# IR_Light_Controller.net
KiCad netlist of a schematic drawn in EAGLE
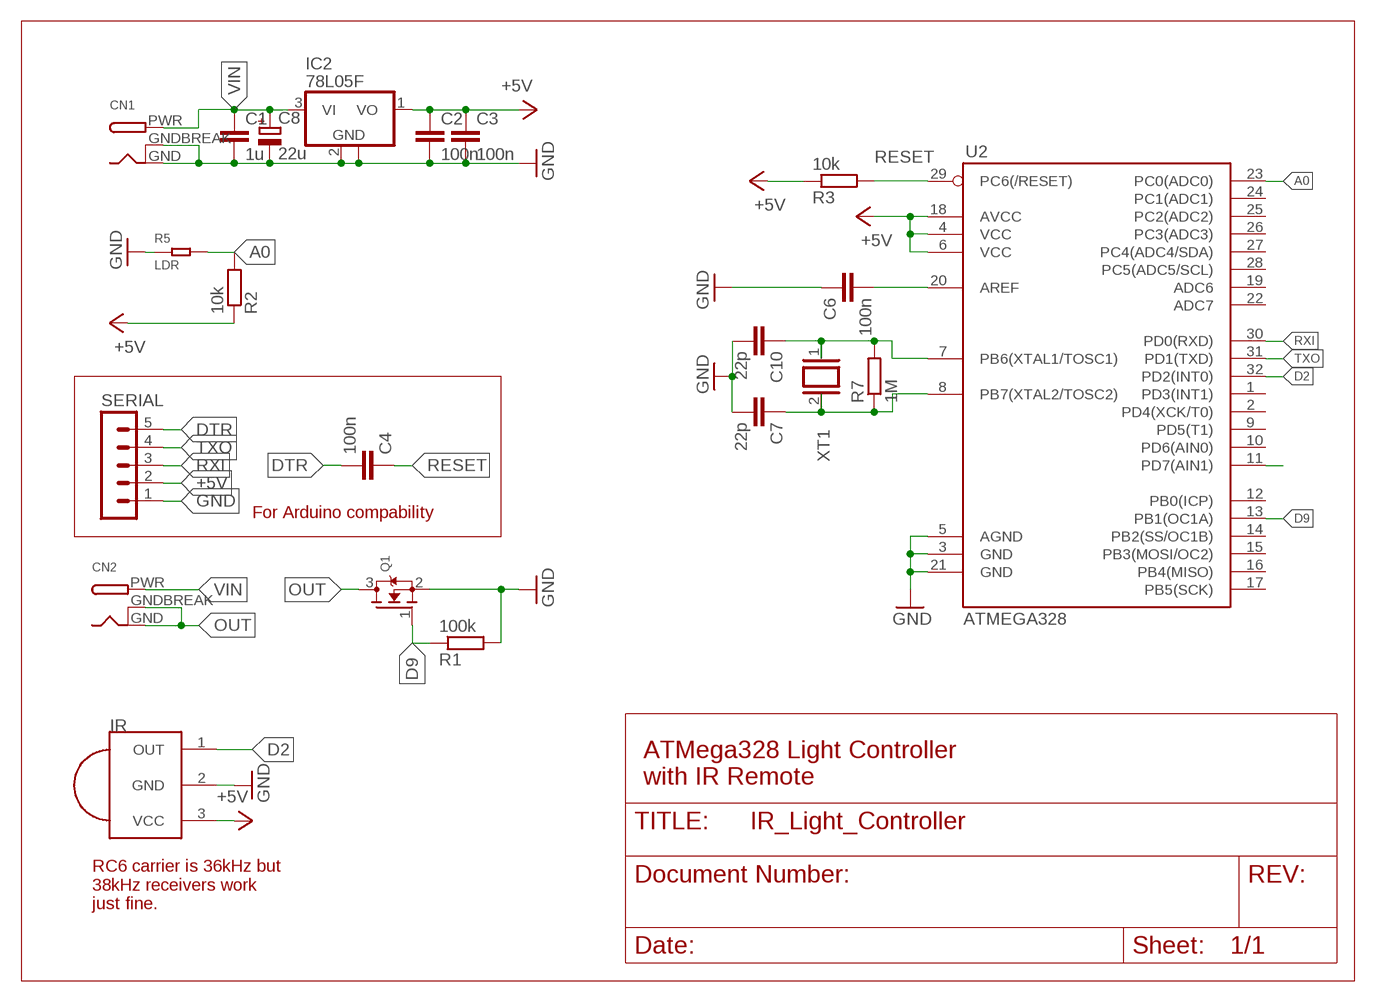
[diagram p0: schematic, sheet 1]

(export (version "E")
  (design (tool "Eeschema 10.0.6"))
  (components
    (comp (ref "C1")
      (value "1u")
      (footprint "eagle-import:C0805")
      (libsource (lib "eagle-import") (part "C-EUC0805"))
    )
    (comp (ref "C2")
      (value "100n")
      (footprint "eagle-import:C0805")
      (libsource (lib "eagle-import") (part "C-EUC0805"))
    )
    (comp (ref "C3")
      (value "100n")
      (footprint "eagle-import:C0805")
      (libsource (lib "eagle-import") (part "C-EUC0805"))
    )
    (comp (ref "C4")
      (value "100n")
      (footprint "eagle-import:C0805K")
      (libsource (lib "eagle-import") (part "C-EUC0805K"))
    )
    (comp (ref "C6")
      (value "100n")
      (footprint "eagle-import:C0805K")
      (libsource (lib "eagle-import") (part "C-EUC0805K"))
    )
    (comp (ref "C7")
      (value "22p")
      (footprint "eagle-import:C0805K")
      (libsource (lib "eagle-import") (part "C-EUC0805K"))
    )
    (comp (ref "C8")
      (value "22u")
      (footprint "eagle-import:E2-4")
      (libsource (lib "eagle-import") (part "CPOL-EUE2-4"))
    )
    (comp (ref "C10")
      (value "22p")
      (footprint "eagle-import:C0805K")
      (libsource (lib "eagle-import") (part "C-EUC0805K"))
    )
    (comp (ref "CN1")
      (value "DCBARRELPTH")
      (footprint "eagle-import:DCJACK_2MM_PTH")
      (libsource (lib "eagle-import") (part "DCBARRELPTH"))
    )
    (comp (ref "CN2")
      (value "DCBARRELPTH")
      (footprint "eagle-import:DCJACK_2MM_PTH")
      (libsource (lib "eagle-import") (part "DCBARRELPTH"))
    )
    (comp (ref "IC2")
      (value "78L05F")
      (footprint "eagle-import:SOT89")
      (libsource (lib "eagle-import") (part "78LF05"))
    )
    (comp (ref "IR")
      (value "PNA460XM")
      (footprint "eagle-import:PNA460XM")
      (libsource (lib "eagle-import") (part "PNA460XM"))
    )
    (comp (ref "Q1")
      (value "MOSFET-NWAVE")
      (footprint "eagle-import:SOT23-W")
      (libsource (lib "eagle-import") (part "MOSFET-NWAVE"))
    )
    (comp (ref "R1")
      (value "100k")
      (footprint "eagle-import:M0805")
      (libsource (lib "eagle-import") (part "R-EU_M0805"))
    )
    (comp (ref "R2")
      (value "10k")
      (footprint "eagle-import:M0805")
      (libsource (lib "eagle-import") (part "R-EU_M0805"))
    )
    (comp (ref "R3")
      (value "10k")
      (footprint "eagle-import:M0805")
      (libsource (lib "eagle-import") (part "R-EU_M0805"))
    )
    (comp (ref "R5")
      (value "LDR")
      (footprint "eagle-import:PR-2.8-4.2X4.9MM")
      (fields (field (name "MPN") "LDR-VT90N2"))
      (libsource (lib "eagle-import") (part "DIP-RES-LDR(2P-D2.3X3.7MM)"))
    )
    (comp (ref "R7")
      (value "1M")
      (footprint "eagle-import:M0805")
      (libsource (lib "eagle-import") (part "R-EU_M0805"))
    )
    (comp (ref "SERIAL")
      (value "MA05-1")
      (footprint "eagle-import:MA05-1")
      (libsource (lib "eagle-import") (part "MA05-1"))
    )
    (comp (ref "U2")
      (value "ATMEGA328")
      (footprint "eagle-import:TQFP32-08")
      (libsource (lib "eagle-import") (part "ATMEGA168"))
    )
    (comp (ref "XT1")
      (value "XTAL/S")
      (footprint "eagle-import:QS")
      (libsource (lib "eagle-import") (part "XTAL/S"))
    )
  )
  (nets
    (net (code "1") (name "+5V") (class "Default")
      (node (ref "C2") (pin "1") (pinfunction "1_1") (pintype "passive"))
      (node (ref "C3") (pin "1") (pinfunction "1_1") (pintype "passive"))
      (node (ref "IC2") (pin "1") (pinfunction "VO_1") (pintype "passive"))
      (node (ref "IR") (pin "3") (pinfunction "VCC_3") (pintype "power_in"))
      (node (ref "R2") (pin "1") (pinfunction "1_1") (pintype "passive"))
      (node (ref "R3") (pin "1") (pinfunction "1_1") (pintype "passive"))
      (node (ref "SERIAL") (pin "2") (pinfunction "2_2") (pintype "passive"))
      (node (ref "U2") (pin "18") (pinfunction "AVCC_18") (pintype "bidirectional"))
      (node (ref "U2") (pin "4") (pinfunction "VCC_4") (pintype "bidirectional"))
      (node (ref "U2") (pin "6") (pinfunction "VCC_6") (pintype "bidirectional"))
    )
    (net (code "2") (name "A0") (class "Default")
      (node (ref "R2") (pin "2") (pinfunction "2_2") (pintype "passive"))
      (node (ref "R5") (pin "2") (pinfunction "2_2") (pintype "passive"))
      (node (ref "U2") (pin "23") (pinfunction "PC0(ADC0)_23") (pintype "bidirectional"))
    )
    (net (code "3") (name "D2") (class "Default")
      (node (ref "IR") (pin "1") (pinfunction "OUT_1") (pintype "output"))
      (node (ref "U2") (pin "32") (pinfunction "PD2(INT0)_32") (pintype "bidirectional"))
    )
    (net (code "4") (name "D9") (class "Default")
      (node (ref "Q1") (pin "1") (pinfunction "G_1") (pintype "bidirectional"))
      (node (ref "R1") (pin "1") (pinfunction "1_1") (pintype "passive"))
      (node (ref "U2") (pin "13") (pinfunction "PB1(OC1A)_13") (pintype "bidirectional"))
    )
    (net (code "5") (name "DTR") (class "Default")
      (node (ref "C4") (pin "2") (pinfunction "2_2") (pintype "passive"))
      (node (ref "SERIAL") (pin "5") (pinfunction "5_5") (pintype "passive"))
    )
    (net (code "6") (name "GND") (class "Default")
      (node (ref "C1") (pin "2") (pinfunction "2_2") (pintype "passive"))
      (node (ref "C10") (pin "2") (pinfunction "2_2") (pintype "passive"))
      (node (ref "C2") (pin "2") (pinfunction "2_2") (pintype "passive"))
      (node (ref "C3") (pin "2") (pinfunction "2_2") (pintype "passive"))
      (node (ref "C6") (pin "1") (pinfunction "1_1") (pintype "passive"))
      (node (ref "C7") (pin "2") (pinfunction "2_2") (pintype "passive"))
      (node (ref "C8") (pin "-") (pinfunction "-_-") (pintype "passive"))
      (node (ref "CN1") (pin "GND") (pinfunction "GND_GND") (pintype "power_in"))
      (node (ref "CN1") (pin "GNDBREAK") (pinfunction "GNDBREAK_GNDBREAK") (pintype "power_in"))
      (node (ref "IC2") (pin "2") (pinfunction "GND_2") (pintype "passive"))
      (node (ref "IC2") (pin "2@1") (pinfunction "GND_2@1") (pintype "passive"))
      (node (ref "IR") (pin "2") (pinfunction "GND_2") (pintype "power_in"))
      (node (ref "Q1") (pin "2") (pinfunction "S_2") (pintype "bidirectional"))
      (node (ref "R1") (pin "2") (pinfunction "2_2") (pintype "passive"))
      (node (ref "R5") (pin "1") (pinfunction "1_1") (pintype "passive"))
      (node (ref "SERIAL") (pin "1") (pinfunction "1_1") (pintype "passive"))
      (node (ref "U2") (pin "21") (pinfunction "GND_21") (pintype "bidirectional"))
      (node (ref "U2") (pin "3") (pinfunction "GND_3") (pintype "bidirectional"))
      (node (ref "U2") (pin "5") (pinfunction "AGND_5") (pintype "bidirectional"))
    )
    (net (code "7") (name "Net-(U2-AREF)") (class "Default")
      (node (ref "C6") (pin "2") (pinfunction "2_2") (pintype "passive"))
      (node (ref "U2") (pin "20") (pinfunction "AREF_20") (pintype "bidirectional"))
    )
    (net (code "8") (name "Net-(U2-PB6(XTAL1{slash}TOSC1))") (class "Default")
      (node (ref "C10") (pin "1") (pinfunction "1_1") (pintype "passive"))
      (node (ref "R7") (pin "2") (pinfunction "2_2") (pintype "passive"))
      (node (ref "U2") (pin "7") (pinfunction "PB6(XTAL1/TOSC1)_7") (pintype "bidirectional"))
      (node (ref "XT1") (pin "1") (pinfunction "1_1") (pintype "passive"))
    )
    (net (code "9") (name "Net-(U2-PB7(XTAL2{slash}TOSC2))") (class "Default")
      (node (ref "C7") (pin "1") (pinfunction "1_1") (pintype "passive"))
      (node (ref "R7") (pin "1") (pinfunction "1_1") (pintype "passive"))
      (node (ref "U2") (pin "8") (pinfunction "PB7(XTAL2/TOSC2)_8") (pintype "bidirectional"))
      (node (ref "XT1") (pin "2") (pinfunction "2_2") (pintype "passive"))
    )
    (net (code "10") (name "OUT") (class "Default")
      (node (ref "CN2") (pin "GND") (pinfunction "GND_GND") (pintype "power_in"))
      (node (ref "CN2") (pin "GNDBREAK") (pinfunction "GNDBREAK_GNDBREAK") (pintype "power_in"))
      (node (ref "Q1") (pin "3") (pinfunction "D_3") (pintype "bidirectional"))
    )
    (net (code "11") (name "RESET") (class "Default")
      (node (ref "C4") (pin "1") (pinfunction "1_1") (pintype "passive"))
      (node (ref "R3") (pin "2") (pinfunction "2_2") (pintype "passive"))
      (node (ref "U2") (pin "29") (pinfunction "PC6(/RESET)_29") (pintype "bidirectional"))
    )
    (net (code "12") (name "RXI") (class "Default")
      (node (ref "SERIAL") (pin "3") (pinfunction "3_3") (pintype "passive"))
      (node (ref "U2") (pin "30") (pinfunction "PD0(RXD)_30") (pintype "bidirectional"))
    )
    (net (code "13") (name "TXO") (class "Default")
      (node (ref "SERIAL") (pin "4") (pinfunction "4_4") (pintype "passive"))
      (node (ref "U2") (pin "31") (pinfunction "PD1(TXD)_31") (pintype "bidirectional"))
    )
    (net (code "14") (name "VIN") (class "Default")
      (node (ref "C1") (pin "1") (pinfunction "1_1") (pintype "passive"))
      (node (ref "C8") (pin "+") (pinfunction "+_+") (pintype "passive"))
      (node (ref "CN1") (pin "PWR") (pinfunction "PWR_PWR") (pintype "power_in"))
      (node (ref "CN2") (pin "PWR") (pinfunction "PWR_PWR") (pintype "power_in"))
      (node (ref "IC2") (pin "3") (pinfunction "VI_3") (pintype "input"))
    )
    (net (code "15") (name "unconnected-(U2-ADC6-Pad19)") (class "Default")
      (node (ref "U2") (pin "19") (pinfunction "ADC6_19") (pintype "bidirectional"))
    )
    (net (code "16") (name "unconnected-(U2-ADC7-Pad22)") (class "Default")
      (node (ref "U2") (pin "22") (pinfunction "ADC7_22") (pintype "bidirectional"))
    )
    (net (code "17") (name "unconnected-(U2-PB0(ICP)-Pad12)") (class "Default")
      (node (ref "U2") (pin "12") (pinfunction "PB0(ICP)_12") (pintype "bidirectional"))
    )
    (net (code "18") (name "unconnected-(U2-PB2(SS{slash}OC1B)-Pad14)") (class "Default")
      (node (ref "U2") (pin "14") (pinfunction "PB2(SS/OC1B)_14") (pintype "bidirectional"))
    )
    (net (code "19") (name "unconnected-(U2-PB3(MOSI{slash}OC2)-Pad15)") (class "Default")
      (node (ref "U2") (pin "15") (pinfunction "PB3(MOSI/OC2)_15") (pintype "bidirectional"))
    )
    (net (code "20") (name "unconnected-(U2-PB4(MISO)-Pad16)") (class "Default")
      (node (ref "U2") (pin "16") (pinfunction "PB4(MISO)_16") (pintype "bidirectional"))
    )
    (net (code "21") (name "unconnected-(U2-PB5(SCK)-Pad17)") (class "Default")
      (node (ref "U2") (pin "17") (pinfunction "PB5(SCK)_17") (pintype "bidirectional"))
    )
    (net (code "22") (name "unconnected-(U2-PC1(ADC1)-Pad24)") (class "Default")
      (node (ref "U2") (pin "24") (pinfunction "PC1(ADC1)_24") (pintype "bidirectional"))
    )
    (net (code "23") (name "unconnected-(U2-PC2(ADC2)-Pad25)") (class "Default")
      (node (ref "U2") (pin "25") (pinfunction "PC2(ADC2)_25") (pintype "bidirectional"))
    )
    (net (code "24") (name "unconnected-(U2-PC3(ADC3)-Pad26)") (class "Default")
      (node (ref "U2") (pin "26") (pinfunction "PC3(ADC3)_26") (pintype "bidirectional"))
    )
    (net (code "25") (name "unconnected-(U2-PC4(ADC4{slash}SDA)-Pad27)") (class "Default")
      (node (ref "U2") (pin "27") (pinfunction "PC4(ADC4/SDA)_27") (pintype "bidirectional"))
    )
    (net (code "26") (name "unconnected-(U2-PC5(ADC5{slash}SCL)-Pad28)") (class "Default")
      (node (ref "U2") (pin "28") (pinfunction "PC5(ADC5/SCL)_28") (pintype "bidirectional"))
    )
    (net (code "27") (name "unconnected-(U2-PD3(INT1)-Pad1)") (class "Default")
      (node (ref "U2") (pin "1") (pinfunction "PD3(INT1)_1") (pintype "bidirectional"))
    )
    (net (code "28") (name "unconnected-(U2-PD4(XCK{slash}T0)-Pad2)") (class "Default")
      (node (ref "U2") (pin "2") (pinfunction "PD4(XCK/T0)_2") (pintype "bidirectional"))
    )
    (net (code "29") (name "unconnected-(U2-PD5(T1)-Pad9)") (class "Default")
      (node (ref "U2") (pin "9") (pinfunction "PD5(T1)_9") (pintype "bidirectional"))
    )
    (net (code "30") (name "unconnected-(U2-PD6(AIN0)-Pad10)") (class "Default")
      (node (ref "U2") (pin "10") (pinfunction "PD6(AIN0)_10") (pintype "bidirectional"))
    )
    (net (code "31") (name "unconnected-(U2-PD7(AIN1)-Pad11)") (class "Default")
      (node (ref "U2") (pin "11") (pinfunction "PD7(AIN1)_11") (pintype "bidirectional"))
    )
  )
)
